# ProPrj_KernRePeter_2025-12-13.net
KiCad netlist of a schematic drawn in EasyEDA Pro
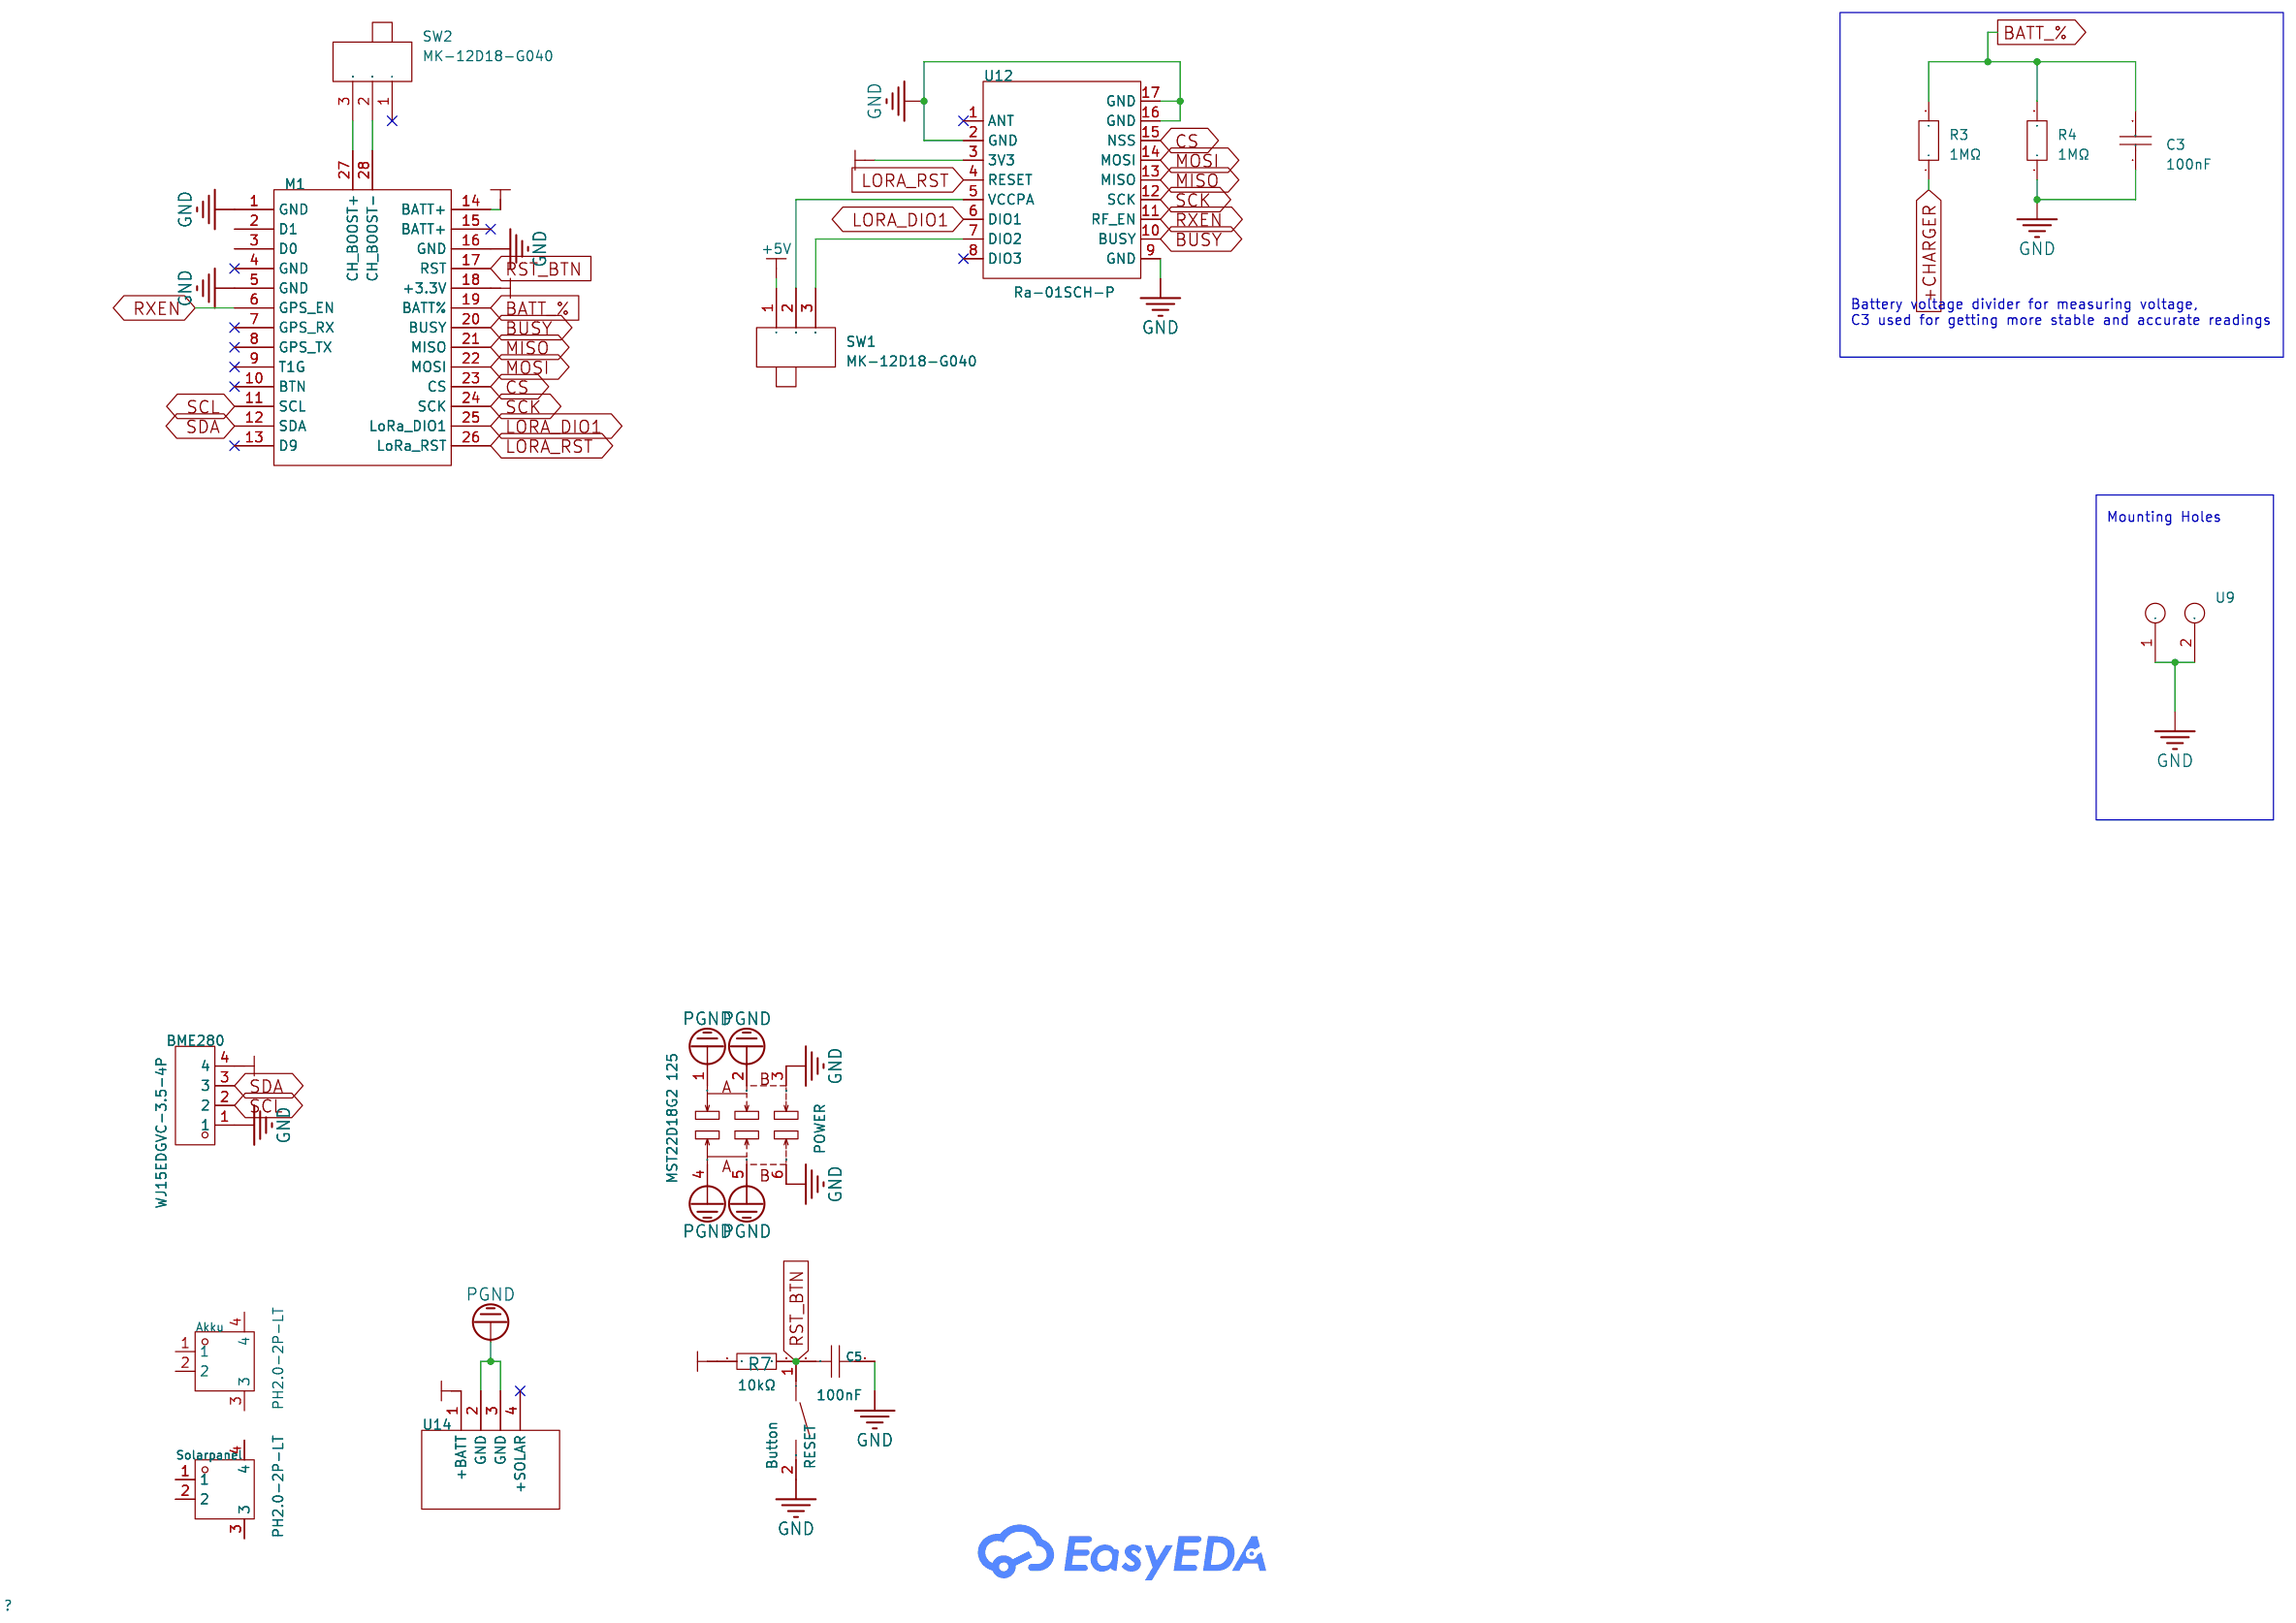
[diagram p0: schematic sheet]

(export (version "E")
  (design (tool "Eeschema 10.0.6"))
  (components
    (comp (ref "Akku")
      (value "PH2.0-2P-LT")
      (footprint "easyedapro:CONN-SMD_PH2.0-1X2PW")
      (fields (field (name "Manufacturer") "CAX(创都)"))
      (libsource (lib "easyedapro") (part "PH2.0-2P-LT"))
    )
    (comp (ref "BME280")
      (value "WJ15EDGVC-3.5-4P")
      (footprint "easyedapro:CONN-TH_WJ15EDGVC-3.5-4P")
      (fields (field (name "Manufacturer") "KANGNEX(康奈克斯电气)"))
      (libsource (lib "easyedapro") (part "WJ15EDGVC-3.5-4P_C5241856"))
    )
    (comp (ref "C3")
      (value "100nF")
      (footprint "easyedapro:C0805")
      (description "Capacitance:100nF Tolerance:±5% Tolerance:±5% Voltage Rating:50V Temperature Coefficient:X7R")
      (fields (field (name "Manufacturer Part") "0805B104J500NT") (field (name "Manufacturer") "FH(风华)"))
      (libsource (lib "easyedapro") (part "0805B104J500NT"))
    )
    (comp (ref "C5")
      (value "100nF")
      (footprint "easyedapro:C0603")
      (description "Capacitance:100nF Tolerance:±10% Tolerance:±10% Voltage Rating:50V Temperature Coefficient:X7R")
      (fields
        (field (name "Manufacturer Part") "CL10B104KB8NNNC")
        (field (name "Manufacturer") "SAMSUNG(三星)")
      )
      (libsource (lib "easyedapro") (part "CL10B104KB8NNNC"))
    )
    (comp (ref "M1")
      (value "ProMicro_NRF52840")
      (footprint "easyedapro:ProMicro_NRF52840")
      (libsource (lib "easyedapro") (part "ProMicro_NRF52840"))
    )
    (comp (ref "POWER")
      (value "MST22D18G2 125")
      (footprint "easyedapro:SW-SMD_MST22D18G2")
      (fields (field (name "Manufacturer") "SHOU HAN(首韩)"))
      (libsource (lib "easyedapro") (part "MST22D18G2 125"))
    )
    (comp (ref "R3")
      (value "1MΩ")
      (footprint "easyedapro:R0805")
      (fields (field (name "Manufacturer Part") "RT0805BRD071ML") (field (name "Manufacturer") "YAGEO(国巨)"))
      (libsource (lib "easyedapro") (part "RT0805BRD071ML"))
    )
    (comp (ref "R4")
      (value "1MΩ")
      (footprint "easyedapro:R0805")
      (fields (field (name "Manufacturer Part") "RT0805BRD071ML") (field (name "Manufacturer") "YAGEO(国巨)"))
      (libsource (lib "easyedapro") (part "RT0805BRD071ML"))
    )
    (comp (ref "R7")
      (value "10kΩ")
      (footprint "easyedapro:R0603")
      (fields
        (field (name "Manufacturer Part") "0603WAF1002T5E")
        (field (name "Manufacturer") "UNI-ROYAL(厚声)")
      )
      (libsource (lib "easyedapro") (part "0603WAF1002T5E"))
    )
    (comp (ref "RESET")
      (value "Button")
      (footprint "easyedapro:SW-SMD_L3.9-W3.0-P4.45")
      (fields (field (name "Manufacturer Part") "TS-1088-AR02016") (field (name "Manufacturer") "XUNPU(讯普)"))
      (libsource (lib "easyedapro") (part "TS-1088-AR02016"))
    )
    (comp (ref "Solarpanel")
      (value "PH2.0-2P-LT")
      (footprint "easyedapro:CONN-SMD_PH2.0-1X2PW")
      (fields (field (name "Manufacturer") "CAX(创都)"))
      (libsource (lib "easyedapro") (part "PH2.0-2P-LT"))
    )
    (comp (ref "SW1")
      (value "MK-12D18-G040")
      (footprint "easyedapro:SW-TH_MK-12D18-G040")
      (fields (field (name "Manufacturer") "G-Switch(品赞)"))
      (libsource (lib "easyedapro") (part "MK-12D18-G040"))
    )
    (comp (ref "SW2")
      (value "MK-12D18-G040")
      (footprint "easyedapro:SW-TH_MK-12D18-G040")
      (fields (field (name "Manufacturer") "G-Switch(品赞)"))
      (libsource (lib "easyedapro") (part "MK-12D18-G040"))
    )
    (comp (ref "U9")
      (value "~")
      (footprint "easyedapro:MountingHole_ES101590")
      (libsource (lib "easyedapro") (part "MountingHoles_ES101590"))
    )
    (comp (ref "U12")
      (value "Ra-01SCH-P")
      (footprint "easyedapro:WIRELM-SMD_RA-01SCH-P")
      (fields (field (name "Manufacturer") "Ai-Thinker(安信可)"))
      (libsource (lib "easyedapro") (part "RA-01SCH-P"))
    )
    (comp (ref "U14")
      (value "~")
      (footprint "easyedapro:MPPT_Charging_Board")
      (libsource (lib "easyedapro") (part "CN3791 MPPT Solar Charger v1.0"))
    )
  )
  (nets
    (net (code "1") (name "+3.3V") (class "Default")
      (node (ref "BME280") (pin "4") (pinfunction "4_4") (pintype "unspecified"))
      (node (ref "M1") (pin "18") (pinfunction "+3.3V_18") (pintype "unspecified"))
      (node (ref "R7") (pin "1") (pinfunction "1_1") (pintype "input"))
      (node (ref "U12") (pin "3") (pinfunction "3V3_3") (pintype "unspecified"))
    )
    (net (code "2") (name "+5V") (class "Default")
      (node (ref "SW1") (pin "1") (pinfunction "1_1") (pintype "unspecified"))
    )
    (net (code "3") (name "+CHARGER") (class "Default")
      (node (ref "M1") (pin "14") (pinfunction "BATT+_14") (pintype "unspecified"))
      (node (ref "R3") (pin "1") (pinfunction "1_1") (pintype "input"))
      (node (ref "U14") (pin "1") (pinfunction "+BATT_1") (pintype "unspecified"))
    )
    (net (code "4") (name "BATT_%") (class "Default")
      (node (ref "C3") (pin "2") (pinfunction "2_2") (pintype "input"))
      (node (ref "M1") (pin "19") (pinfunction "BATT%_19") (pintype "input"))
      (node (ref "R3") (pin "2") (pinfunction "2_2") (pintype "input"))
      (node (ref "R4") (pin "2") (pinfunction "2_2") (pintype "input"))
    )
    (net (code "5") (name "BUSY") (class "Default")
      (node (ref "M1") (pin "20") (pinfunction "BUSY_20") (pintype "bidirectional"))
      (node (ref "U12") (pin "10") (pinfunction "BUSY_10") (pintype "unspecified"))
    )
    (net (code "6") (name "CS") (class "Default")
      (node (ref "M1") (pin "23") (pinfunction "CS_23") (pintype "bidirectional"))
      (node (ref "U12") (pin "15") (pinfunction "NSS_15") (pintype "unspecified"))
    )
    (net (code "7") (name "GND") (class "Default")
      (node (ref "BME280") (pin "1") (pinfunction "1_1") (pintype "unspecified"))
      (node (ref "C3") (pin "1") (pinfunction "1_1") (pintype "input"))
      (node (ref "C5") (pin "2") (pinfunction "2_2") (pintype "input"))
      (node (ref "M1") (pin "1") (pinfunction "GND_1") (pintype "unspecified"))
      (node (ref "M1") (pin "16") (pinfunction "GND_16") (pintype "unspecified"))
      (node (ref "M1") (pin "5") (pinfunction "GND_5") (pintype "unspecified"))
      (node (ref "POWER") (pin "3") (pinfunction "3_3") (pintype "unspecified"))
      (node (ref "POWER") (pin "6") (pinfunction "6_6") (pintype "unspecified"))
      (node (ref "R4") (pin "1") (pinfunction "1_1") (pintype "input"))
      (node (ref "RESET") (pin "2") (pinfunction "2_2") (pintype "unspecified"))
      (node (ref "U12") (pin "16") (pinfunction "GND_16") (pintype "unspecified"))
      (node (ref "U12") (pin "17") (pinfunction "GND_17") (pintype "unspecified"))
      (node (ref "U12") (pin "2") (pinfunction "GND_2") (pintype "unspecified"))
      (node (ref "U12") (pin "9") (pinfunction "GND_9") (pintype "unspecified"))
      (node (ref "U9") (pin "1") (pinfunction "1_1") (pintype "unspecified"))
      (node (ref "U9") (pin "2") (pinfunction "2_2") (pintype "unspecified"))
    )
    (net (code "8") (name "LORA_DIO1") (class "Default")
      (node (ref "M1") (pin "25") (pinfunction "LoRa_DIO1_25") (pintype "output"))
      (node (ref "U12") (pin "6") (pinfunction "DIO1_6") (pintype "unspecified"))
    )
    (net (code "9") (name "LORA_RST") (class "Default")
      (node (ref "M1") (pin "26") (pinfunction "LoRa_RST_26") (pintype "output"))
      (node (ref "U12") (pin "4") (pinfunction "RESET_4") (pintype "unspecified"))
    )
    (net (code "10") (name "MISO") (class "Default")
      (node (ref "M1") (pin "21") (pinfunction "MISO_21") (pintype "bidirectional"))
      (node (ref "U12") (pin "13") (pinfunction "MISO_13") (pintype "unspecified"))
    )
    (net (code "11") (name "MOSI") (class "Default")
      (node (ref "M1") (pin "22") (pinfunction "MOSI_22") (pintype "bidirectional"))
      (node (ref "U12") (pin "14") (pinfunction "MOSI_14") (pintype "unspecified"))
    )
    (net (code "12") (name "Net-(M1-CH_BOOST+)") (class "Default")
      (node (ref "M1") (pin "27") (pinfunction "CH_BOOST+_27") (pintype "input"))
      (node (ref "SW2") (pin "3") (pinfunction "3_3") (pintype "unspecified"))
    )
    (net (code "13") (name "Net-(M1-CH_BOOST-)") (class "Default")
      (node (ref "M1") (pin "28") (pinfunction "CH_BOOST-_28") (pintype "input"))
      (node (ref "SW2") (pin "2") (pinfunction "2_2") (pintype "unspecified"))
    )
    (net (code "14") (name "Net-(U12-DIO2)") (class "Default")
      (node (ref "SW1") (pin "3") (pinfunction "3_3") (pintype "unspecified"))
      (node (ref "U12") (pin "7") (pinfunction "DIO2_7") (pintype "unspecified"))
    )
    (net (code "15") (name "Net-(U12-VCCPA)") (class "Default")
      (node (ref "SW1") (pin "2") (pinfunction "2_2") (pintype "unspecified"))
      (node (ref "U12") (pin "5") (pinfunction "VCCPA_5") (pintype "unspecified"))
    )
    (net (code "16") (name "PGND") (class "Default")
      (node (ref "POWER") (pin "1") (pinfunction "1_1") (pintype "unspecified"))
      (node (ref "POWER") (pin "2") (pinfunction "2_2") (pintype "unspecified"))
      (node (ref "POWER") (pin "4") (pinfunction "4_4") (pintype "unspecified"))
      (node (ref "POWER") (pin "5") (pinfunction "5_5") (pintype "unspecified"))
      (node (ref "U14") (pin "2") (pinfunction "GND_2") (pintype "unspecified"))
      (node (ref "U14") (pin "3") (pinfunction "GND_3") (pintype "unspecified"))
    )
    (net (code "17") (name "RST_BTN") (class "Default")
      (node (ref "C5") (pin "1") (pinfunction "1_1") (pintype "input"))
      (node (ref "M1") (pin "17") (pinfunction "RST_17") (pintype "input"))
      (node (ref "R7") (pin "2") (pinfunction "2_2") (pintype "input"))
      (node (ref "RESET") (pin "1") (pinfunction "1_1") (pintype "unspecified"))
    )
    (net (code "18") (name "RXEN") (class "Default")
      (node (ref "M1") (pin "6") (pinfunction "GPS_EN_6") (pintype "input"))
      (node (ref "U12") (pin "11") (pinfunction "RF_EN_11") (pintype "unspecified"))
    )
    (net (code "19") (name "SCK") (class "Default")
      (node (ref "M1") (pin "24") (pinfunction "SCK_24") (pintype "bidirectional"))
      (node (ref "U12") (pin "12") (pinfunction "SCK_12") (pintype "unspecified"))
    )
    (net (code "20") (name "SCL") (class "Default")
      (node (ref "BME280") (pin "2") (pinfunction "2_2") (pintype "unspecified"))
      (node (ref "M1") (pin "11") (pinfunction "SCL_11") (pintype "bidirectional"))
    )
    (net (code "21") (name "SDA") (class "Default")
      (node (ref "BME280") (pin "3") (pinfunction "3_3") (pintype "unspecified"))
      (node (ref "M1") (pin "12") (pinfunction "SDA_12") (pintype "bidirectional"))
    )
    (net (code "22") (name "unconnected-(Akku-Pad1)") (class "Default")
      (node (ref "Akku") (pin "1") (pinfunction "1_1") (pintype "input"))
    )
    (net (code "23") (name "unconnected-(Akku-Pad2)") (class "Default")
      (node (ref "Akku") (pin "2") (pinfunction "2_2") (pintype "input"))
    )
    (net (code "24") (name "unconnected-(Akku-Pad3)") (class "Default")
      (node (ref "Akku") (pin "3") (pinfunction "3_3") (pintype "input"))
    )
    (net (code "25") (name "unconnected-(Akku-Pad4)") (class "Default")
      (node (ref "Akku") (pin "4") (pinfunction "4_4") (pintype "input"))
    )
    (net (code "26") (name "unconnected-(M1-BATT+-Pad15)") (class "Default")
      (node (ref "M1") (pin "15") (pinfunction "BATT+_15") (pintype "unspecified+no_connect"))
    )
    (net (code "27") (name "unconnected-(M1-BTN-Pad10)") (class "Default")
      (node (ref "M1") (pin "10") (pinfunction "BTN_10") (pintype "input+no_connect"))
    )
    (net (code "28") (name "unconnected-(M1-D0-Pad3)") (class "Default")
      (node (ref "M1") (pin "3") (pinfunction "D0_3") (pintype "input"))
    )
    (net (code "29") (name "unconnected-(M1-D1-Pad2)") (class "Default")
      (node (ref "M1") (pin "2") (pinfunction "D1_2") (pintype "input"))
    )
    (net (code "30") (name "unconnected-(M1-D9-Pad13)") (class "Default")
      (node (ref "M1") (pin "13") (pinfunction "D9_13") (pintype "bidirectional+no_connect"))
    )
    (net (code "31") (name "unconnected-(M1-GND-Pad4)") (class "Default")
      (node (ref "M1") (pin "4") (pinfunction "GND_4") (pintype "unspecified+no_connect"))
    )
    (net (code "32") (name "unconnected-(M1-GPS_RX-Pad7)") (class "Default")
      (node (ref "M1") (pin "7") (pinfunction "GPS_RX_7") (pintype "input+no_connect"))
    )
    (net (code "33") (name "unconnected-(M1-GPS_TX-Pad8)") (class "Default")
      (node (ref "M1") (pin "8") (pinfunction "GPS_TX_8") (pintype "input+no_connect"))
    )
    (net (code "34") (name "unconnected-(M1-T1G-Pad9)") (class "Default")
      (node (ref "M1") (pin "9") (pinfunction "T1G_9") (pintype "input+no_connect"))
    )
    (net (code "35") (name "unconnected-(SW2-Pad1)") (class "Default")
      (node (ref "SW2") (pin "1") (pinfunction "1_1") (pintype "unspecified+no_connect"))
    )
    (net (code "36") (name "unconnected-(Solarpanel-Pad1)") (class "Default")
      (node (ref "Solarpanel") (pin "1") (pinfunction "1_1") (pintype "input"))
    )
    (net (code "37") (name "unconnected-(Solarpanel-Pad2)") (class "Default")
      (node (ref "Solarpanel") (pin "2") (pinfunction "2_2") (pintype "input"))
    )
    (net (code "38") (name "unconnected-(Solarpanel-Pad3)") (class "Default")
      (node (ref "Solarpanel") (pin "3") (pinfunction "3_3") (pintype "input"))
    )
    (net (code "39") (name "unconnected-(Solarpanel-Pad4)") (class "Default")
      (node (ref "Solarpanel") (pin "4") (pinfunction "4_4") (pintype "input"))
    )
    (net (code "40") (name "unconnected-(U12-ANT-Pad1)") (class "Default")
      (node (ref "U12") (pin "1") (pinfunction "ANT_1") (pintype "unspecified+no_connect"))
    )
    (net (code "41") (name "unconnected-(U12-DIO3-Pad8)") (class "Default")
      (node (ref "U12") (pin "8") (pinfunction "DIO3_8") (pintype "unspecified+no_connect"))
    )
    (net (code "42") (name "unconnected-(U14-+SOLAR-Pad4)") (class "Default")
      (node (ref "U14") (pin "4") (pinfunction "+SOLAR_4") (pintype "unspecified+no_connect"))
    )
  )
)
